# MCU.net
KiCad netlist of a schematic drawn in Altium Designer
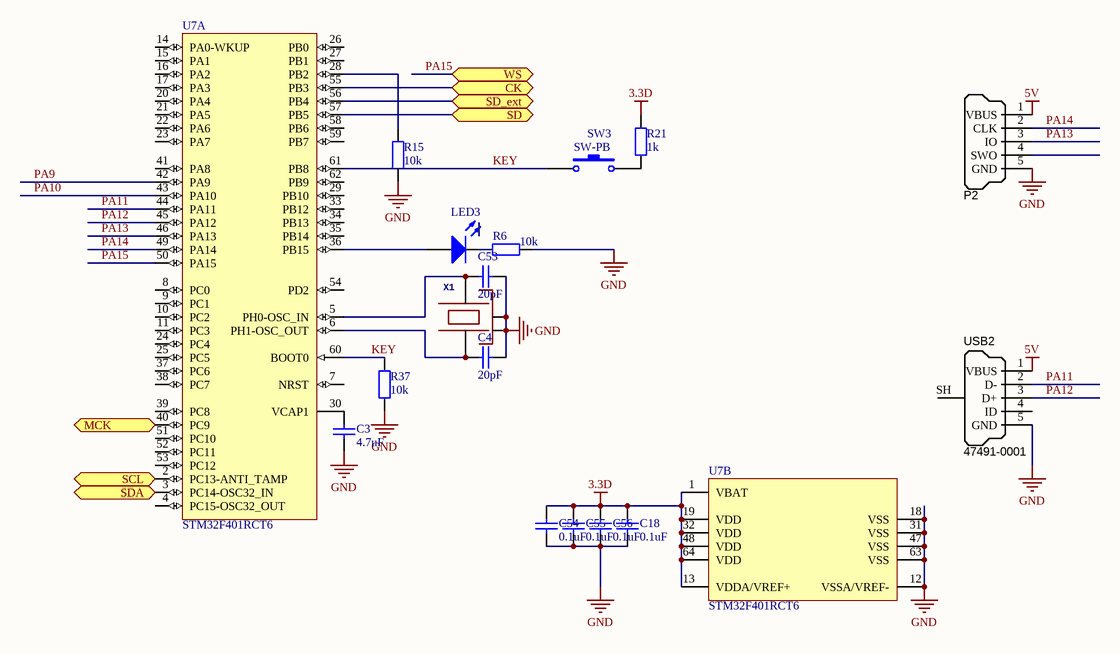
[diagram p0: MCU.SchDoc]

(export (version "E")
  (design (tool "Eeschema 10.0.6"))
  (components
    (comp (ref "C3")
      (value "4.7uF")
      (footprint "0603L")
      (description "Capacitor")
      (fields (field (name "Comment") "Cap") (field (name "PUBLISHER") "Altium Limited"))
      (libsource (lib "RTC6705") (part "Cap"))
    )
    (comp (ref "C4")
      (value "20pF")
      (footprint "0402")
      (description "Capacitor")
      (fields (field (name "Comment") "Cap") (field (name "PUBLISHER") "Altium Limited"))
      (libsource (lib "RTC6705") (part "Cap"))
    )
    (comp (ref "C18")
      (value "0.1uF")
      (footprint "0402")
      (description "Capacitor")
      (fields (field (name "Comment") "Cap") (field (name "PUBLISHER") "Altium Limited"))
      (libsource (lib "RTC6705") (part "Cap"))
    )
    (comp (ref "C53")
      (value "20pF")
      (footprint "0402")
      (description "Capacitor")
      (fields (field (name "Comment") "Cap") (field (name "PUBLISHER") "Altium Limited"))
      (libsource (lib "RTC6705") (part "Cap"))
    )
    (comp (ref "C54")
      (value "0.1uF")
      (footprint "0402")
      (description "Capacitor")
      (fields (field (name "Comment") "Cap") (field (name "PUBLISHER") "Altium Limited"))
      (libsource (lib "RTC6705") (part "Cap"))
    )
    (comp (ref "C55")
      (value "0.1uF")
      (footprint "0402")
      (description "Capacitor")
      (fields (field (name "Comment") "Cap") (field (name "PUBLISHER") "Altium Limited"))
      (libsource (lib "RTC6705") (part "Cap"))
    )
    (comp (ref "C56")
      (value "0.1uF")
      (footprint "0402")
      (description "Capacitor")
      (fields (field (name "Comment") "Cap") (field (name "PUBLISHER") "Altium Limited"))
      (libsource (lib "RTC6705") (part "Cap"))
    )
    (comp (ref "LED3")
      (value "LED0")
      (footprint "0603")
      (description "Typical INFRARED GaAs LED")
      (fields (field (name "PUBLISHER") "Altium Limited"))
      (libsource (lib "Miscellaneous Devices") (part "LED0"))
    )
    (comp (ref "P2")
      (value "SWD_MicroUSB")
      (footprint "MICRO-YZX")
      (description "Connector SMD USB Micro Type B middle mount")
      (libsource (lib "sch") (part "SWD_MicroUSB"))
    )
    (comp (ref "R6")
      (value "10k")
      (footprint "0402")
      (description "Resistor")
      (fields (field (name "PUBLISHER") "Altium Limited"))
      (libsource (lib "Miscellaneous Devices") (part "Res2"))
    )
    (comp (ref "R15")
      (value "10k")
      (footprint "0402")
      (description "Resistor")
      (fields (field (name "PUBLISHER") "Altium Limited"))
      (libsource (lib "") (part "Res2_2"))
    )
    (comp (ref "R21")
      (value "1k")
      (footprint "0402")
      (description "Resistor")
      (fields (field (name "PUBLISHER") "Altium Limited"))
      (libsource (lib "") (part "Res2_1"))
    )
    (comp (ref "R37")
      (value "10k")
      (footprint "0402")
      (description "Resistor")
      (fields (field (name "Comment") "Res2") (field (name "PUBLISHER") "Altium Limited"))
      (libsource (lib "RTC6705") (part "Res2"))
    )
    (comp (ref "SW3")
      (value "SW-PB")
      (footprint "SW3x4")
      (description "Switch")
      (fields (field (name "PUBLISHER") "Altium Limited"))
      (libsource (lib "Miscellaneous Devices") (part "SW-PB"))
    )
    (comp (ref "U7")
      (value "STM32F401RCT6")
      (footprint "STM-LQFP64_N")
      (fields (field (name "MANUFACTURER") "STMicroelectronics"))
      (libsource (lib "STMicroelectronics STM32 F4") (part "STM32F401RCT6"))
    )
    (comp (ref "USB2")
      (value "USB Micro Type B")
      (footprint "MICRO-YZX")
      (description "Connector SMD USB Micro Type B middle mount")
      (fields (field (name "MANUFACTURER PART NUMBER 1") "47491-0001"))
      (libsource (lib "PBL - Connectors") (part "USB_Micro_TypeB"))
    )
    (comp (ref "X1")
      (value "24.000 KHz 3.2x2.5mm 8-10pf")
      (footprint "OSCILLATOR-2.5x2.0")
      (description "Crystal Oscillator in 3.2x2.5 SMD")
      (libsource (lib "pixhawk2") (part "OSCILLATOR-3.2X2.5"))
    )
  )
  (nets
    (net (code "1") (name "/CK") (class "Default")
      (node (ref "U7") (pin "55") (pinfunction "PB3_55") (pintype "bidirectional"))
    )
    (net (code "2") (name "/KEY") (class "Default")
      (node (ref "R37") (pin "2") (pinfunction "2_2") (pintype "passive"))
      (node (ref "SW3") (pin "1") (pinfunction "1_1") (pintype "passive"))
      (node (ref "U7") (pin "60") (pinfunction "BOOT0_60") (pintype "input"))
      (node (ref "U7") (pin "61") (pinfunction "PB8_61") (pintype "bidirectional"))
    )
    (net (code "3") (name "/MCK") (class "Default")
      (node (ref "U7") (pin "40") (pinfunction "PC9_40") (pintype "bidirectional"))
    )
    (net (code "4") (name "/PA9") (class "Default")
      (node (ref "U7") (pin "42") (pinfunction "PA9_42") (pintype "bidirectional"))
    )
    (net (code "5") (name "/PA10") (class "Default")
      (node (ref "U7") (pin "43") (pinfunction "PA10_43") (pintype "bidirectional"))
    )
    (net (code "6") (name "/PA11") (class "Default")
      (node (ref "U7") (pin "44") (pinfunction "PA11_44") (pintype "bidirectional"))
      (node (ref "USB2") (pin "2") (pinfunction "D-_2") (pintype "passive"))
    )
    (net (code "7") (name "/PA12") (class "Default")
      (node (ref "U7") (pin "45") (pinfunction "PA12_45") (pintype "bidirectional"))
      (node (ref "USB2") (pin "3") (pinfunction "D+_3") (pintype "passive"))
    )
    (net (code "8") (name "/PA13") (class "Default")
      (node (ref "P2") (pin "3") (pinfunction "IO_3") (pintype "passive"))
      (node (ref "U7") (pin "46") (pinfunction "PA13_46") (pintype "bidirectional"))
    )
    (net (code "9") (name "/PA14") (class "Default")
      (node (ref "P2") (pin "2") (pinfunction "CLK_2") (pintype "passive"))
      (node (ref "U7") (pin "49") (pinfunction "PA14_49") (pintype "bidirectional"))
    )
    (net (code "10") (name "/PA15") (class "Default")
      (node (ref "U7") (pin "50") (pinfunction "PA15_50") (pintype "bidirectional"))
    )
    (net (code "11") (name "/SCL") (class "Default")
      (node (ref "U7") (pin "2") (pinfunction "PC13-ANTI_TAMP_2") (pintype "bidirectional"))
    )
    (net (code "12") (name "/SD") (class "Default")
      (node (ref "U7") (pin "57") (pinfunction "PB5_57") (pintype "bidirectional"))
    )
    (net (code "13") (name "/SDA") (class "Default")
      (node (ref "U7") (pin "3") (pinfunction "PC14-OSC32_IN_3") (pintype "bidirectional"))
    )
    (net (code "14") (name "/SD_ext") (class "Default")
      (node (ref "U7") (pin "56") (pinfunction "PB4_56") (pintype "bidirectional"))
    )
    (net (code "15") (name "3.3D") (class "Default")
      (node (ref "C18") (pin "2") (pinfunction "2_2") (pintype "passive"))
      (node (ref "C54") (pin "2") (pinfunction "2_2") (pintype "passive"))
      (node (ref "C55") (pin "2") (pinfunction "2_2") (pintype "passive"))
      (node (ref "C56") (pin "2") (pinfunction "2_2") (pintype "passive"))
      (node (ref "R21") (pin "2") (pinfunction "2_2") (pintype "passive"))
      (node (ref "U7") (pin "1") (pinfunction "VBAT_1") (pintype "power_in"))
      (node (ref "U7") (pin "13") (pinfunction "VDDA/VREF+_13") (pintype "power_in"))
      (node (ref "U7") (pin "19") (pinfunction "VDD_19") (pintype "power_in"))
      (node (ref "U7") (pin "32") (pinfunction "VDD_32") (pintype "power_in"))
      (node (ref "U7") (pin "48") (pinfunction "VDD_48") (pintype "power_in"))
      (node (ref "U7") (pin "64") (pinfunction "VDD_64") (pintype "power_in"))
    )
    (net (code "16") (name "5V") (class "Default")
      (node (ref "P2") (pin "1") (pinfunction "VBUS_1") (pintype "passive"))
      (node (ref "USB2") (pin "1") (pinfunction "VBUS_1") (pintype "passive"))
    )
    (net (code "17") (name "GND") (class "Default")
      (node (ref "C18") (pin "1") (pinfunction "1_1") (pintype "passive"))
      (node (ref "C3") (pin "1") (pinfunction "1_1") (pintype "passive"))
      (node (ref "C4") (pin "1") (pinfunction "1_1") (pintype "passive"))
      (node (ref "C53") (pin "1") (pinfunction "1_1") (pintype "passive"))
      (node (ref "C54") (pin "1") (pinfunction "1_1") (pintype "passive"))
      (node (ref "C55") (pin "1") (pinfunction "1_1") (pintype "passive"))
      (node (ref "C56") (pin "1") (pinfunction "1_1") (pintype "passive"))
      (node (ref "P2") (pin "5") (pinfunction "GND_5") (pintype "passive"))
      (node (ref "R15") (pin "2") (pinfunction "2_2") (pintype "passive"))
      (node (ref "R37") (pin "1") (pinfunction "1_1") (pintype "passive"))
      (node (ref "R6") (pin "2") (pinfunction "2_2") (pintype "passive"))
      (node (ref "U7") (pin "12") (pinfunction "VSSA/VREF-_12") (pintype "power_in"))
      (node (ref "U7") (pin "18") (pinfunction "VSS_18") (pintype "power_in"))
      (node (ref "U7") (pin "31") (pinfunction "VSS_31") (pintype "power_in"))
      (node (ref "U7") (pin "47") (pinfunction "VSS_47") (pintype "power_in"))
      (node (ref "U7") (pin "63") (pinfunction "VSS_63") (pintype "power_in"))
      (node (ref "USB2") (pin "5") (pinfunction "GND_5") (pintype "passive"))
      (node (ref "X1") (pin "2") (pinfunction "NC_2_2") (pintype "open_emitter"))
      (node (ref "X1") (pin "4") (pinfunction "NC_4_4") (pintype "open_emitter"))
    )
    (net (code "18") (name "Net-(LED3-A)") (class "Default")
      (node (ref "LED3") (pin "1") (pinfunction "A_1") (pintype "passive"))
      (node (ref "U7") (pin "36") (pinfunction "PB15_36") (pintype "bidirectional"))
    )
    (net (code "19") (name "Net-(LED3-K)") (class "Default")
      (node (ref "LED3") (pin "2") (pinfunction "K_2") (pintype "passive"))
      (node (ref "R6") (pin "1") (pinfunction "1_1") (pintype "passive"))
    )
    (net (code "20") (name "Net-(R21-Pad1)") (class "Default")
      (node (ref "R21") (pin "1") (pinfunction "1_1") (pintype "passive"))
      (node (ref "SW3") (pin "2") (pinfunction "2_2") (pintype "passive"))
    )
    (net (code "21") (name "Net-(U7A-PB2)") (class "Default")
      (node (ref "R15") (pin "1") (pinfunction "1_1") (pintype "passive"))
      (node (ref "U7") (pin "28") (pinfunction "PB2_28") (pintype "bidirectional"))
    )
    (net (code "22") (name "Net-(U7A-PH0-OSC_IN)") (class "Default")
      (node (ref "C53") (pin "2") (pinfunction "2_2") (pintype "passive"))
      (node (ref "U7") (pin "5") (pinfunction "PH0-OSC_IN_5") (pintype "bidirectional"))
      (node (ref "X1") (pin "3") (pinfunction "3_3") (pintype "passive"))
    )
    (net (code "23") (name "Net-(U7A-PH1-OSC_OUT)") (class "Default")
      (node (ref "C4") (pin "2") (pinfunction "2_2") (pintype "passive"))
      (node (ref "U7") (pin "6") (pinfunction "PH1-OSC_OUT_6") (pintype "bidirectional"))
      (node (ref "X1") (pin "1") (pinfunction "1_1") (pintype "passive"))
    )
    (net (code "24") (name "Net-(U7A-VCAP1)") (class "Default")
      (node (ref "C3") (pin "2") (pinfunction "2_2") (pintype "passive"))
      (node (ref "U7") (pin "30") (pinfunction "VCAP1_30") (pintype "power_in"))
    )
    (net (code "25") (name "unconnected-(P2-SWO-Pad4)") (class "Default")
      (node (ref "P2") (pin "4") (pinfunction "SWO_4") (pintype "passive"))
    )
    (net (code "26") (name "unconnected-(U7A-NRST-Pad7)") (class "Default")
      (node (ref "U7") (pin "7") (pinfunction "NRST_7") (pintype "bidirectional"))
    )
    (net (code "27") (name "unconnected-(U7A-PA0-WKUP-Pad14)") (class "Default")
      (node (ref "U7") (pin "14") (pinfunction "PA0-WKUP_14") (pintype "bidirectional"))
    )
    (net (code "28") (name "unconnected-(U7A-PA1-Pad15)") (class "Default")
      (node (ref "U7") (pin "15") (pinfunction "PA1_15") (pintype "bidirectional"))
    )
    (net (code "29") (name "unconnected-(U7A-PA2-Pad16)") (class "Default")
      (node (ref "U7") (pin "16") (pinfunction "PA2_16") (pintype "bidirectional"))
    )
    (net (code "30") (name "unconnected-(U7A-PA3-Pad17)") (class "Default")
      (node (ref "U7") (pin "17") (pinfunction "PA3_17") (pintype "bidirectional"))
    )
    (net (code "31") (name "unconnected-(U7A-PA4-Pad20)") (class "Default")
      (node (ref "U7") (pin "20") (pinfunction "PA4_20") (pintype "bidirectional"))
    )
    (net (code "32") (name "unconnected-(U7A-PA5-Pad21)") (class "Default")
      (node (ref "U7") (pin "21") (pinfunction "PA5_21") (pintype "bidirectional"))
    )
    (net (code "33") (name "unconnected-(U7A-PA6-Pad22)") (class "Default")
      (node (ref "U7") (pin "22") (pinfunction "PA6_22") (pintype "bidirectional"))
    )
    (net (code "34") (name "unconnected-(U7A-PA7-Pad23)") (class "Default")
      (node (ref "U7") (pin "23") (pinfunction "PA7_23") (pintype "bidirectional"))
    )
    (net (code "35") (name "unconnected-(U7A-PA8-Pad41)") (class "Default")
      (node (ref "U7") (pin "41") (pinfunction "PA8_41") (pintype "bidirectional"))
    )
    (net (code "36") (name "unconnected-(U7A-PB0-Pad26)") (class "Default")
      (node (ref "U7") (pin "26") (pinfunction "PB0_26") (pintype "bidirectional"))
    )
    (net (code "37") (name "unconnected-(U7A-PB1-Pad27)") (class "Default")
      (node (ref "U7") (pin "27") (pinfunction "PB1_27") (pintype "bidirectional"))
    )
    (net (code "38") (name "unconnected-(U7A-PB6-Pad58)") (class "Default")
      (node (ref "U7") (pin "58") (pinfunction "PB6_58") (pintype "bidirectional"))
    )
    (net (code "39") (name "unconnected-(U7A-PB7-Pad59)") (class "Default")
      (node (ref "U7") (pin "59") (pinfunction "PB7_59") (pintype "bidirectional"))
    )
    (net (code "40") (name "unconnected-(U7A-PB9-Pad62)") (class "Default")
      (node (ref "U7") (pin "62") (pinfunction "PB9_62") (pintype "bidirectional"))
    )
    (net (code "41") (name "unconnected-(U7A-PB10-Pad29)") (class "Default")
      (node (ref "U7") (pin "29") (pinfunction "PB10_29") (pintype "bidirectional"))
    )
    (net (code "42") (name "unconnected-(U7A-PB12-Pad33)") (class "Default")
      (node (ref "U7") (pin "33") (pinfunction "PB12_33") (pintype "bidirectional"))
    )
    (net (code "43") (name "unconnected-(U7A-PB13-Pad34)") (class "Default")
      (node (ref "U7") (pin "34") (pinfunction "PB13_34") (pintype "bidirectional"))
    )
    (net (code "44") (name "unconnected-(U7A-PB14-Pad35)") (class "Default")
      (node (ref "U7") (pin "35") (pinfunction "PB14_35") (pintype "bidirectional"))
    )
    (net (code "45") (name "unconnected-(U7A-PC0-Pad8)") (class "Default")
      (node (ref "U7") (pin "8") (pinfunction "PC0_8") (pintype "bidirectional"))
    )
    (net (code "46") (name "unconnected-(U7A-PC1-Pad9)") (class "Default")
      (node (ref "U7") (pin "9") (pinfunction "PC1_9") (pintype "bidirectional"))
    )
    (net (code "47") (name "unconnected-(U7A-PC2-Pad10)") (class "Default")
      (node (ref "U7") (pin "10") (pinfunction "PC2_10") (pintype "bidirectional"))
    )
    (net (code "48") (name "unconnected-(U7A-PC3-Pad11)") (class "Default")
      (node (ref "U7") (pin "11") (pinfunction "PC3_11") (pintype "bidirectional"))
    )
    (net (code "49") (name "unconnected-(U7A-PC4-Pad24)") (class "Default")
      (node (ref "U7") (pin "24") (pinfunction "PC4_24") (pintype "bidirectional"))
    )
    (net (code "50") (name "unconnected-(U7A-PC5-Pad25)") (class "Default")
      (node (ref "U7") (pin "25") (pinfunction "PC5_25") (pintype "bidirectional"))
    )
    (net (code "51") (name "unconnected-(U7A-PC6-Pad37)") (class "Default")
      (node (ref "U7") (pin "37") (pinfunction "PC6_37") (pintype "bidirectional"))
    )
    (net (code "52") (name "unconnected-(U7A-PC7-Pad38)") (class "Default")
      (node (ref "U7") (pin "38") (pinfunction "PC7_38") (pintype "bidirectional"))
    )
    (net (code "53") (name "unconnected-(U7A-PC8-Pad39)") (class "Default")
      (node (ref "U7") (pin "39") (pinfunction "PC8_39") (pintype "bidirectional"))
    )
    (net (code "54") (name "unconnected-(U7A-PC10-Pad51)") (class "Default")
      (node (ref "U7") (pin "51") (pinfunction "PC10_51") (pintype "bidirectional"))
    )
    (net (code "55") (name "unconnected-(U7A-PC11-Pad52)") (class "Default")
      (node (ref "U7") (pin "52") (pinfunction "PC11_52") (pintype "bidirectional"))
    )
    (net (code "56") (name "unconnected-(U7A-PC12-Pad53)") (class "Default")
      (node (ref "U7") (pin "53") (pinfunction "PC12_53") (pintype "bidirectional"))
    )
    (net (code "57") (name "unconnected-(U7A-PC15-OSC32_OUT-Pad4)") (class "Default")
      (node (ref "U7") (pin "4") (pinfunction "PC15-OSC32_OUT_4") (pintype "bidirectional"))
    )
    (net (code "58") (name "unconnected-(U7A-PD2-Pad54)") (class "Default")
      (node (ref "U7") (pin "54") (pinfunction "PD2_54") (pintype "bidirectional"))
    )
    (net (code "59") (name "unconnected-(USB2-ID-Pad4)") (class "Default")
      (node (ref "USB2") (pin "4") (pinfunction "ID_4") (pintype "passive"))
    )
    (net (code "60") (name "unconnected-(USB2-Shell-PadSH)") (class "Default")
      (node (ref "USB2") (pin "SH") (pinfunction "Shell_SH") (pintype "passive"))
    )
  )
)
